# DIAGONAL_POLYPHONIC_SEQUENCER_SIMPLER_VE.net
KiCad netlist of a schematic drawn in EAGLE
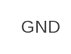
[diagram p0: schematic, sheet 1, part 1 of 2]
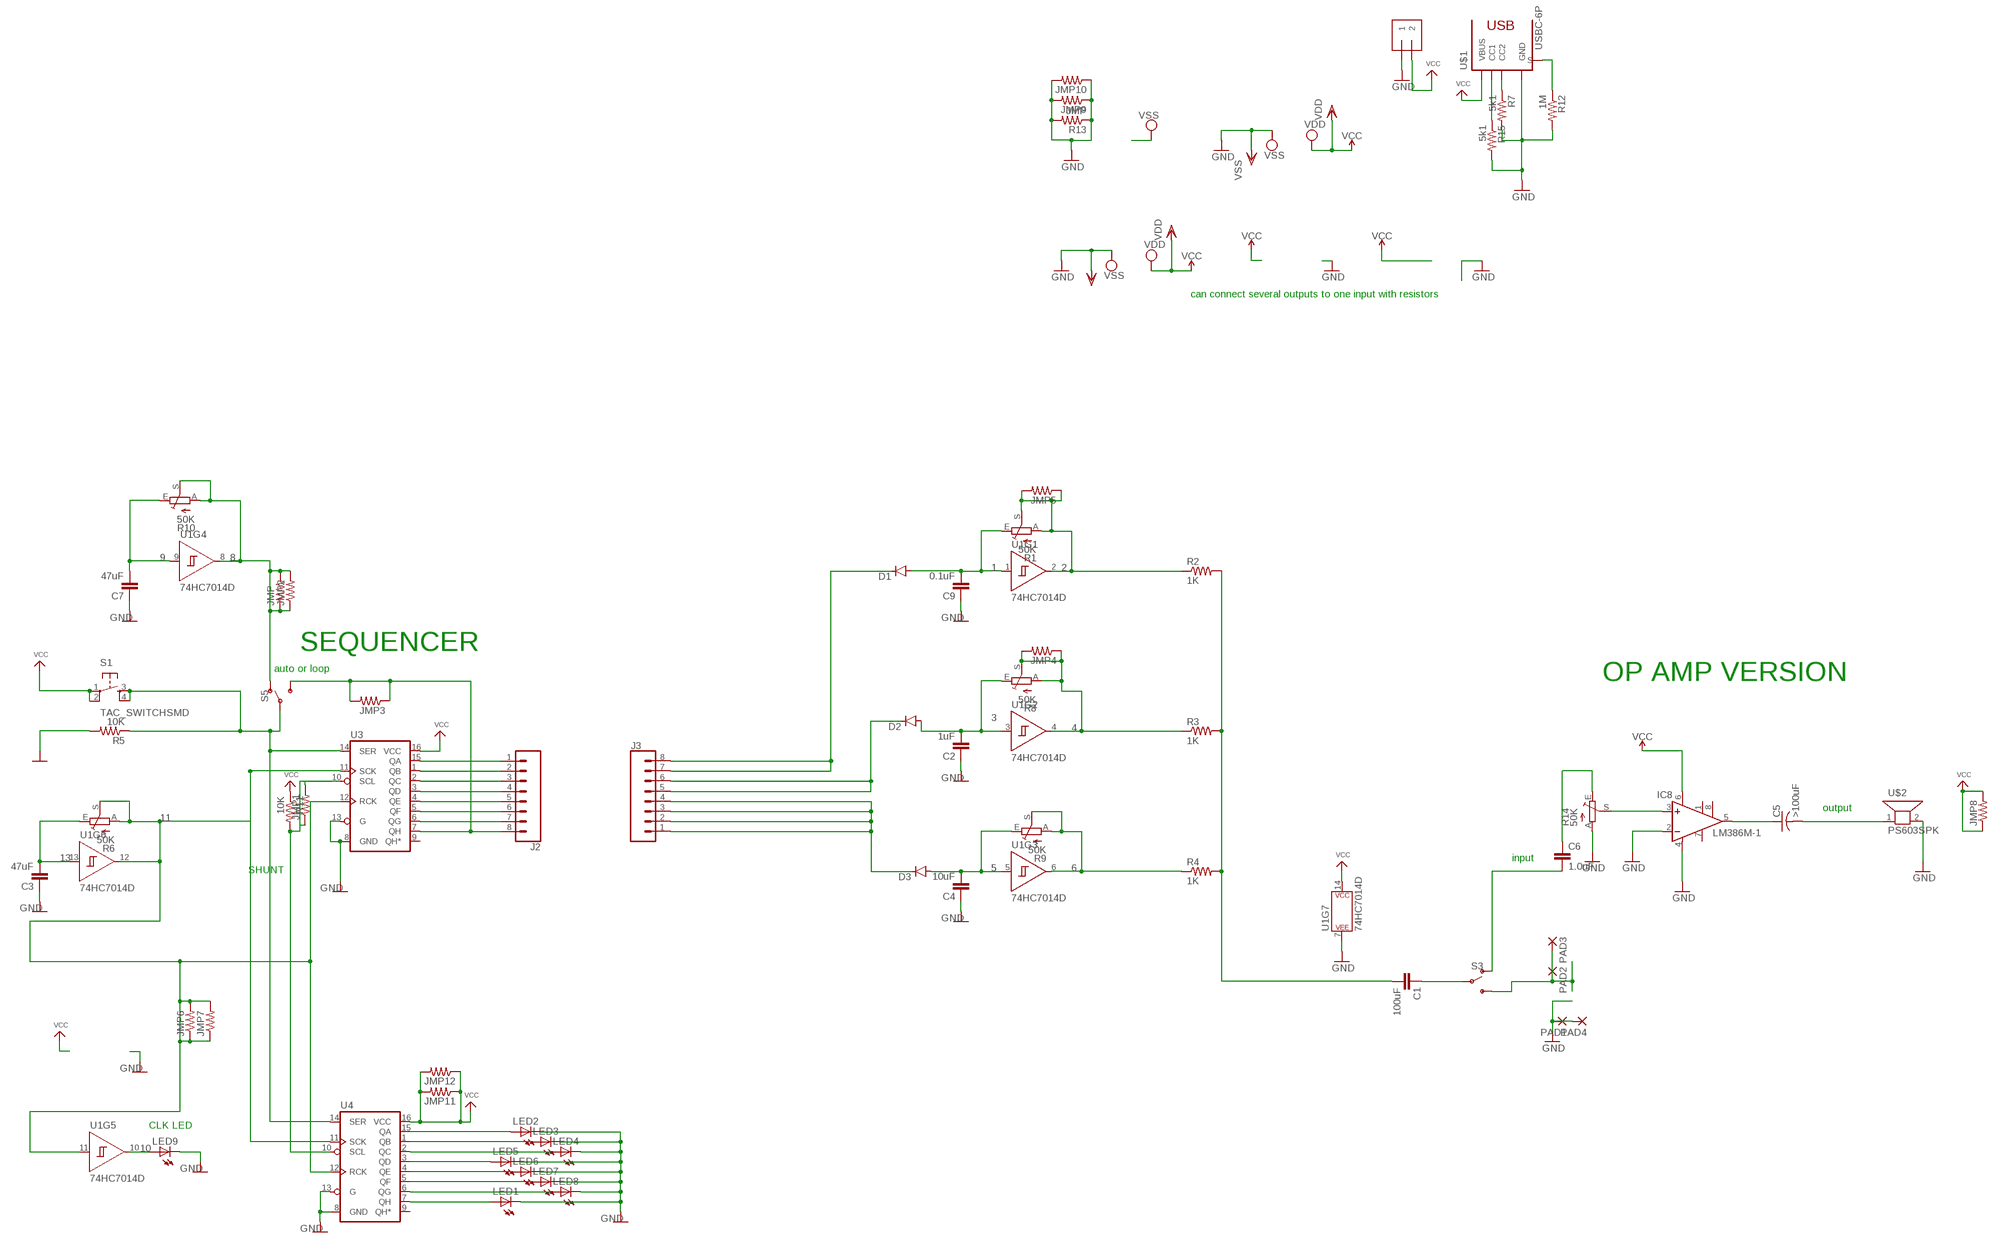
[diagram p1: schematic, sheet 1, part 2 of 2]

(export (version "E")
  (design (tool "Eeschema 10.0.6"))
  (components
    (comp (ref "C1")
      (value "100uF")
      (footprint "eagle-import:1206")
      (libsource (lib "eagle-import") (part "1.0UF-1206-50V-10%"))
    )
    (comp (ref "C2")
      (value "1uF")
      (footprint "eagle-import:1206")
      (libsource (lib "eagle-import") (part "1.0UF-1206-50V-10%"))
    )
    (comp (ref "C3")
      (value "47uF")
      (footprint "eagle-import:1206")
      (libsource (lib "eagle-import") (part "1.0UF-1206-50V-10%"))
    )
    (comp (ref "C4")
      (value "10uF")
      (footprint "eagle-import:1206")
      (libsource (lib "eagle-import") (part "1.0UF-1206-50V-10%"))
    )
    (comp (ref "C5")
      (value ">100uF")
      (footprint "eagle-import:C1206")
      (libsource (lib "eagle-import") (part "C-USC1206"))
    )
    (comp (ref "C6")
      (value "1.0uF")
      (footprint "eagle-import:1206")
      (libsource (lib "eagle-import") (part "1.0UF-1206-50V-10%"))
    )
    (comp (ref "C7")
      (value "47uF")
      (footprint "eagle-import:1206")
      (libsource (lib "eagle-import") (part "1.0UF-1206-50V-10%"))
    )
    (comp (ref "C9")
      (value "0.1uF")
      (footprint "eagle-import:1206")
      (libsource (lib "eagle-import") (part "1.0UF-1206-50V-10%"))
    )
    (comp (ref "D1")
      (value "DIODEDO214AA")
      (footprint "eagle-import:DO-214AA")
      (libsource (lib "eagle-import") (part "DIODEDO214AA"))
    )
    (comp (ref "D2")
      (value "DIODEDO214AA")
      (footprint "eagle-import:DO-214AA")
      (libsource (lib "eagle-import") (part "DIODEDO214AA"))
    )
    (comp (ref "D3")
      (value "DIODEDO214AA")
      (footprint "eagle-import:DO-214AA")
      (libsource (lib "eagle-import") (part "DIODEDO214AA"))
    )
    (comp (ref "IC8")
      (value "LM386M-1")
      (footprint "eagle-import:SO08")
      (libsource (lib "eagle-import") (part "LM386?-M1"))
    )
    (comp (ref "J1")
      (value "1X2-3.5MM")
      (footprint "eagle-import:1X2-3.5MM")
      (libsource (lib "eagle-import") (part "1X2-3.5MM"))
    )
    (comp (ref "J2")
      (value "CONN_08SMD-STRAIGHT-ALT-FEMALE")
      (footprint "eagle-import:1X08_SMD_ALT")
      (libsource (lib "eagle-import") (part "CONN_08SMD-STRAIGHT-ALT-FEMALE"))
    )
    (comp (ref "J3")
      (value "CONN_08SMD-STRAIGHT-ALT-FEMALE")
      (footprint "eagle-import:1X08_SMD_ALT")
      (libsource (lib "eagle-import") (part "CONN_08SMD-STRAIGHT-ALT-FEMALE"))
    )
    (comp (ref "JMP")
      (value "R-US_R1206")
      (footprint "eagle-import:R1206")
      (libsource (lib "eagle-import") (part "R-US_R1206"))
    )
    (comp (ref "JMP1")
      (value "R-US_R1206")
      (footprint "eagle-import:R1206")
      (libsource (lib "eagle-import") (part "R-US_R1206"))
    )
    (comp (ref "JMP2")
      (value "R-US_R1206")
      (footprint "eagle-import:R1206")
      (libsource (lib "eagle-import") (part "R-US_R1206"))
    )
    (comp (ref "JMP3")
      (value "R-US_R1206")
      (footprint "eagle-import:R1206")
      (libsource (lib "eagle-import") (part "R-US_R1206"))
    )
    (comp (ref "JMP4")
      (value "R-US_R1206")
      (footprint "eagle-import:R1206")
      (libsource (lib "eagle-import") (part "R-US_R1206"))
    )
    (comp (ref "JMP5")
      (value "R-US_R1206")
      (footprint "eagle-import:R1206")
      (libsource (lib "eagle-import") (part "R-US_R1206"))
    )
    (comp (ref "JMP6")
      (value "R-US_R1206")
      (footprint "eagle-import:R1206")
      (libsource (lib "eagle-import") (part "R-US_R1206"))
    )
    (comp (ref "JMP7")
      (value "R-US_R1206")
      (footprint "eagle-import:R1206")
      (libsource (lib "eagle-import") (part "R-US_R1206"))
    )
    (comp (ref "JMP8")
      (value "R-US_R1206")
      (footprint "eagle-import:R1206")
      (libsource (lib "eagle-import") (part "R-US_R1206"))
    )
    (comp (ref "JMP9")
      (value "R-US_R1206")
      (footprint "eagle-import:R1206")
      (libsource (lib "eagle-import") (part "R-US_R1206"))
    )
    (comp (ref "JMP10")
      (value "R-US_R1206")
      (footprint "eagle-import:R1206")
      (libsource (lib "eagle-import") (part "R-US_R1206"))
    )
    (comp (ref "JMP11")
      (value "R-US_R1206")
      (footprint "eagle-import:R1206")
      (libsource (lib "eagle-import") (part "R-US_R1206"))
    )
    (comp (ref "JMP12")
      (value "R-US_R1206")
      (footprint "eagle-import:R1206")
      (libsource (lib "eagle-import") (part "R-US_R1206"))
    )
    (comp (ref "LED1")
      (value "LEDCHIPLED_1206")
      (footprint "eagle-import:CHIPLED_1206")
      (libsource (lib "eagle-import") (part "LEDCHIPLED_1206"))
    )
    (comp (ref "LED2")
      (value "LEDCHIPLED_1206")
      (footprint "eagle-import:CHIPLED_1206")
      (libsource (lib "eagle-import") (part "LEDCHIPLED_1206"))
    )
    (comp (ref "LED3")
      (value "LEDCHIPLED_1206")
      (footprint "eagle-import:CHIPLED_1206")
      (libsource (lib "eagle-import") (part "LEDCHIPLED_1206"))
    )
    (comp (ref "LED4")
      (value "LEDCHIPLED_1206")
      (footprint "eagle-import:CHIPLED_1206")
      (libsource (lib "eagle-import") (part "LEDCHIPLED_1206"))
    )
    (comp (ref "LED5")
      (value "LEDCHIPLED_1206")
      (footprint "eagle-import:CHIPLED_1206")
      (libsource (lib "eagle-import") (part "LEDCHIPLED_1206"))
    )
    (comp (ref "LED6")
      (value "LEDCHIPLED_1206")
      (footprint "eagle-import:CHIPLED_1206")
      (libsource (lib "eagle-import") (part "LEDCHIPLED_1206"))
    )
    (comp (ref "LED7")
      (value "LEDCHIPLED_1206")
      (footprint "eagle-import:CHIPLED_1206")
      (libsource (lib "eagle-import") (part "LEDCHIPLED_1206"))
    )
    (comp (ref "LED8")
      (value "LEDCHIPLED_1206")
      (footprint "eagle-import:CHIPLED_1206")
      (libsource (lib "eagle-import") (part "LEDCHIPLED_1206"))
    )
    (comp (ref "LED9")
      (value "LEDCHIPLED_1206")
      (footprint "eagle-import:CHIPLED_1206")
      (libsource (lib "eagle-import") (part "LEDCHIPLED_1206"))
    )
    (comp (ref "PAD1")
      (value "SMD5")
      (footprint "eagle-import:SMD2,54-5,08")
      (libsource (lib "eagle-import") (part "SMD5"))
    )
    (comp (ref "PAD2")
      (value "SMD5")
      (footprint "eagle-import:SMD2,54-5,08")
      (libsource (lib "eagle-import") (part "SMD5"))
    )
    (comp (ref "PAD3")
      (value "SMD5")
      (footprint "eagle-import:SMD2,54-5,08")
      (libsource (lib "eagle-import") (part "SMD5"))
    )
    (comp (ref "PAD4")
      (value "SMD5")
      (footprint "eagle-import:SMD2,54-5,08")
      (libsource (lib "eagle-import") (part "SMD5"))
    )
    (comp (ref "R1")
      (value "50K")
      (footprint "eagle-import:CA9V")
      (libsource (lib "eagle-import") (part "TRIM_EU-CA9V"))
    )
    (comp (ref "R2")
      (value "1K")
      (footprint "eagle-import:R1206")
      (libsource (lib "eagle-import") (part "R-US_R1206"))
    )
    (comp (ref "R3")
      (value "1K")
      (footprint "eagle-import:R1206")
      (libsource (lib "eagle-import") (part "R-US_R1206"))
    )
    (comp (ref "R4")
      (value "1K")
      (footprint "eagle-import:R1206")
      (libsource (lib "eagle-import") (part "R-US_R1206"))
    )
    (comp (ref "R5")
      (value "10K")
      (footprint "eagle-import:R1206")
      (libsource (lib "eagle-import") (part "R-US_R1206"))
    )
    (comp (ref "R6")
      (value "50K")
      (footprint "eagle-import:CA9V")
      (libsource (lib "eagle-import") (part "TRIM_EU-CA9V"))
    )
    (comp (ref "R7")
      (value "5k1")
      (footprint "eagle-import:R1206")
      (libsource (lib "eagle-import") (part "R-US_R1206"))
    )
    (comp (ref "R8")
      (value "50K")
      (footprint "eagle-import:CA9V")
      (libsource (lib "eagle-import") (part "TRIM_EU-CA9V"))
    )
    (comp (ref "R9")
      (value "50K")
      (footprint "eagle-import:CA9V")
      (libsource (lib "eagle-import") (part "TRIM_EU-CA9V"))
    )
    (comp (ref "R10")
      (value "50K")
      (footprint "eagle-import:CA9V")
      (libsource (lib "eagle-import") (part "TRIM_EU-CA9V"))
    )
    (comp (ref "R11")
      (value "10K")
      (footprint "eagle-import:R1206")
      (libsource (lib "eagle-import") (part "R-US_R1206"))
    )
    (comp (ref "R12")
      (value "1M")
      (footprint "eagle-import:R1206")
      (libsource (lib "eagle-import") (part "R-US_R1206"))
    )
    (comp (ref "R13")
      (value "JMP")
      (footprint "eagle-import:R1206")
      (libsource (lib "eagle-import") (part "R-US_R1206"))
    )
    (comp (ref "R14")
      (value "50K")
      (footprint "eagle-import:CA9V")
      (libsource (lib "eagle-import") (part "TRIM_EU-CA9V"))
    )
    (comp (ref "R15")
      (value "5k1")
      (footprint "eagle-import:R1206")
      (libsource (lib "eagle-import") (part "R-US_R1206"))
    )
    (comp (ref "S1")
      (value "TAC_SWITCHSMD")
      (footprint "eagle-import:TACTILE-SWITCH-SMD")
      (libsource (lib "eagle-import") (part "TAC_SWITCHSMD"))
    )
    (comp (ref "S3")
      (value "SWITCH-SPDT-SMD-AYZ0202")
      (footprint "eagle-import:SWITCH_DPDT_SMD_AYZ0202")
      (libsource (lib "eagle-import") (part "SWITCH-SPDT-SMD-AYZ0202"))
    )
    (comp (ref "S5")
      (value "SWITCH-SPDT-SMD-AYZ0202")
      (footprint "eagle-import:SWITCH_DPDT_SMD_AYZ0202")
      (libsource (lib "eagle-import") (part "SWITCH-SPDT-SMD-AYZ0202"))
    )
    (comp (ref "U$1")
      (value "USBC-6P")
      (footprint "eagle-import:USCX-06FX-XXMX-01")
      (libsource (lib "eagle-import") (part "USBC-6P"))
    )
    (comp (ref "U$2")
      (value "PS603SPK")
      (footprint "eagle-import:PS603")
      (libsource (lib "eagle-import") (part "PS603SPK"))
    )
    (comp (ref "U1")
      (value "74HC7014D")
      (footprint "eagle-import:SO14")
      (libsource (lib "eagle-import") (part "747014DHC"))
    )
    (comp (ref "U3")
      (value "74595")
      (footprint "eagle-import:TSSOP16")
      (libsource (lib "eagle-import") (part "74595"))
    )
    (comp (ref "U4")
      (value "74595")
      (footprint "eagle-import:TSSOP16")
      (libsource (lib "eagle-import") (part "74595"))
    )
  )
  (nets
    (net (code "1") (name "/1") (class "Default")
      (node (ref "C9") (pin "2") (pinfunction "2_2") (pintype "passive"))
      (node (ref "D1") (pin "A") (pinfunction "A_A") (pintype "passive"))
      (node (ref "R1") (pin "E") (pinfunction "E_E") (pintype "passive"))
      (node (ref "U1") (pin "1") (pinfunction "A_1") (pintype "bidirectional"))
    )
    (net (code "2") (name "/2") (class "Default")
      (node (ref "JMP5") (pin "1") (pinfunction "1_1") (pintype "passive"))
      (node (ref "JMP5") (pin "2") (pinfunction "2_2") (pintype "passive"))
      (node (ref "R1") (pin "A") (pinfunction "A_A") (pintype "passive"))
      (node (ref "R1") (pin "S") (pinfunction "S_S") (pintype "passive"))
      (node (ref "R2") (pin "1") (pinfunction "1_1") (pintype "passive"))
      (node (ref "U1") (pin "2") (pinfunction "Y_2") (pintype "bidirectional"))
    )
    (net (code "3") (name "/3") (class "Default")
      (node (ref "C2") (pin "2") (pinfunction "2_2") (pintype "passive"))
      (node (ref "D2") (pin "A") (pinfunction "A_A") (pintype "passive"))
      (node (ref "R8") (pin "E") (pinfunction "E_E") (pintype "passive"))
      (node (ref "U1") (pin "3") (pinfunction "A_3") (pintype "bidirectional"))
    )
    (net (code "4") (name "/4") (class "Default")
      (node (ref "JMP4") (pin "1") (pinfunction "1_1") (pintype "passive"))
      (node (ref "JMP4") (pin "2") (pinfunction "2_2") (pintype "passive"))
      (node (ref "R3") (pin "1") (pinfunction "1_1") (pintype "passive"))
      (node (ref "R8") (pin "A") (pinfunction "A_A") (pintype "passive"))
      (node (ref "R8") (pin "S") (pinfunction "S_S") (pintype "passive"))
      (node (ref "U1") (pin "4") (pinfunction "Y_4") (pintype "bidirectional"))
    )
    (net (code "5") (name "/5") (class "Default")
      (node (ref "C4") (pin "2") (pinfunction "2_2") (pintype "passive"))
      (node (ref "D3") (pin "A") (pinfunction "A_A") (pintype "passive"))
      (node (ref "R9") (pin "E") (pinfunction "E_E") (pintype "passive"))
      (node (ref "U1") (pin "5") (pinfunction "A_5") (pintype "bidirectional"))
    )
    (net (code "6") (name "/6") (class "Default")
      (node (ref "R4") (pin "1") (pinfunction "1_1") (pintype "passive"))
      (node (ref "R9") (pin "A") (pinfunction "A_A") (pintype "passive"))
      (node (ref "R9") (pin "S") (pinfunction "S_S") (pintype "passive"))
      (node (ref "U1") (pin "6") (pinfunction "Y_6") (pintype "bidirectional"))
    )
    (net (code "7") (name "/8") (class "Default")
      (node (ref "JMP") (pin "1") (pinfunction "1_1") (pintype "passive"))
      (node (ref "JMP") (pin "2") (pinfunction "2_2") (pintype "passive"))
      (node (ref "JMP2") (pin "1") (pinfunction "1_1") (pintype "passive"))
      (node (ref "JMP2") (pin "2") (pinfunction "2_2") (pintype "passive"))
      (node (ref "R10") (pin "A") (pinfunction "A_A") (pintype "passive"))
      (node (ref "R10") (pin "S") (pinfunction "S_S") (pintype "passive"))
      (node (ref "S5") (pin "1") (pinfunction "O_1") (pintype "passive"))
      (node (ref "U1") (pin "8") (pinfunction "Y_8") (pintype "bidirectional"))
    )
    (net (code "8") (name "/9") (class "Default")
      (node (ref "C7") (pin "2") (pinfunction "2_2") (pintype "passive"))
      (node (ref "R10") (pin "E") (pinfunction "E_E") (pintype "passive"))
      (node (ref "U1") (pin "9") (pinfunction "A_9") (pintype "bidirectional"))
    )
    (net (code "9") (name "/10") (class "Default")
      (node (ref "LED9") (pin "A") (pinfunction "A_A") (pintype "passive"))
      (node (ref "U1") (pin "10") (pinfunction "Y_10") (pintype "bidirectional"))
    )
    (net (code "10") (name "/11") (class "Default")
      (node (ref "JMP6") (pin "1") (pinfunction "1_1") (pintype "passive"))
      (node (ref "JMP6") (pin "2") (pinfunction "2_2") (pintype "passive"))
      (node (ref "JMP7") (pin "1") (pinfunction "1_1") (pintype "passive"))
      (node (ref "JMP7") (pin "2") (pinfunction "2_2") (pintype "passive"))
      (node (ref "R6") (pin "A") (pinfunction "A_A") (pintype "passive"))
      (node (ref "R6") (pin "S") (pinfunction "S_S") (pintype "passive"))
      (node (ref "U1") (pin "11") (pinfunction "A_11") (pintype "bidirectional"))
      (node (ref "U1") (pin "12") (pinfunction "Y_12") (pintype "bidirectional"))
      (node (ref "U3") (pin "11") (pinfunction "SCK_11") (pintype "input"))
      (node (ref "U3") (pin "12") (pinfunction "RCK_12") (pintype "input"))
      (node (ref "U4") (pin "11") (pinfunction "SCK_11") (pintype "input"))
      (node (ref "U4") (pin "12") (pinfunction "RCK_12") (pintype "input"))
    )
    (net (code "11") (name "/13") (class "Default")
      (node (ref "C3") (pin "2") (pinfunction "2_2") (pintype "passive"))
      (node (ref "R6") (pin "E") (pinfunction "E_E") (pintype "passive"))
      (node (ref "U1") (pin "13") (pinfunction "A_13") (pintype "bidirectional"))
    )
    (net (code "12") (name "GND") (class "Default")
      (node (ref "C2") (pin "1") (pinfunction "1_1") (pintype "passive"))
      (node (ref "C3") (pin "1") (pinfunction "1_1") (pintype "passive"))
      (node (ref "C4") (pin "1") (pinfunction "1_1") (pintype "passive"))
      (node (ref "C7") (pin "1") (pinfunction "1_1") (pintype "passive"))
      (node (ref "C9") (pin "1") (pinfunction "1_1") (pintype "passive"))
      (node (ref "IC8") (pin "2") (pinfunction "-IN_2") (pintype "input"))
      (node (ref "IC8") (pin "4") (pinfunction "GND_4") (pintype "power_in"))
      (node (ref "J1") (pin "1") (pinfunction "1_1") (pintype "passive"))
      (node (ref "JMP10") (pin "1") (pinfunction "1_1") (pintype "passive"))
      (node (ref "JMP10") (pin "2") (pinfunction "2_2") (pintype "passive"))
      (node (ref "JMP9") (pin "1") (pinfunction "1_1") (pintype "passive"))
      (node (ref "JMP9") (pin "2") (pinfunction "2_2") (pintype "passive"))
      (node (ref "LED1") (pin "C") (pinfunction "C_C") (pintype "passive"))
      (node (ref "LED2") (pin "C") (pinfunction "C_C") (pintype "passive"))
      (node (ref "LED3") (pin "C") (pinfunction "C_C") (pintype "passive"))
      (node (ref "LED4") (pin "C") (pinfunction "C_C") (pintype "passive"))
      (node (ref "LED5") (pin "C") (pinfunction "C_C") (pintype "passive"))
      (node (ref "LED6") (pin "C") (pinfunction "C_C") (pintype "passive"))
      (node (ref "LED7") (pin "C") (pinfunction "C_C") (pintype "passive"))
      (node (ref "LED8") (pin "C") (pinfunction "C_C") (pintype "passive"))
      (node (ref "LED9") (pin "C") (pinfunction "C_C") (pintype "passive"))
      (node (ref "PAD1") (pin "1") (pinfunction "P_1") (pintype "passive"))
      (node (ref "PAD4") (pin "1") (pinfunction "P_1") (pintype "passive"))
      (node (ref "R12") (pin "2") (pinfunction "2_2") (pintype "passive"))
      (node (ref "R13") (pin "1") (pinfunction "1_1") (pintype "passive"))
      (node (ref "R13") (pin "2") (pinfunction "2_2") (pintype "passive"))
      (node (ref "R14") (pin "A") (pinfunction "A_A") (pintype "passive"))
      (node (ref "R15") (pin "2") (pinfunction "2_2") (pintype "passive"))
      (node (ref "R5") (pin "2") (pinfunction "2_2") (pintype "passive"))
      (node (ref "R7") (pin "2") (pinfunction "2_2") (pintype "passive"))
      (node (ref "U$1") (pin "GND1") (pinfunction "GND_GND1") (pintype "power_in"))
      (node (ref "U$1") (pin "GND2") (pinfunction "GND_GND2") (pintype "power_in"))
      (node (ref "U$2") (pin "2") (pinfunction "2_2") (pintype "passive"))
      (node (ref "U1") (pin "7") (pinfunction "P$V-_7") (pintype "bidirectional"))
      (node (ref "U3") (pin "13") (pinfunction "G_13") (pintype "input"))
      (node (ref "U3") (pin "8") (pinfunction "GND_8") (pintype "power_in"))
      (node (ref "U4") (pin "13") (pinfunction "G_13") (pintype "input"))
      (node (ref "U4") (pin "8") (pinfunction "GND_8") (pintype "power_in"))
    )
    (net (code "13") (name "Net-(C1-Pad2)") (class "Default")
      (node (ref "C1") (pin "2") (pinfunction "2_2") (pintype "passive"))
      (node (ref "R2") (pin "2") (pinfunction "2_2") (pintype "passive"))
      (node (ref "R3") (pin "2") (pinfunction "2_2") (pintype "passive"))
      (node (ref "R4") (pin "2") (pinfunction "2_2") (pintype "passive"))
    )
    (net (code "14") (name "Net-(C5-Pad2)") (class "Default")
      (node (ref "C5") (pin "2") (pinfunction "2_2") (pintype "passive"))
      (node (ref "U$2") (pin "1") (pinfunction "1_1") (pintype "passive"))
    )
    (net (code "15") (name "Net-(C6-Pad1)") (class "Default")
      (node (ref "C6") (pin "1") (pinfunction "1_1") (pintype "passive"))
      (node (ref "R14") (pin "E") (pinfunction "E_E") (pintype "passive"))
    )
    (net (code "16") (name "Net-(D1-PadC)") (class "Default")
      (node (ref "D1") (pin "C") (pinfunction "C_C") (pintype "passive"))
      (node (ref "J3") (pin "7") (pinfunction "7_7") (pintype "passive"))
      (node (ref "J3") (pin "8") (pinfunction "8_8") (pintype "passive"))
    )
    (net (code "17") (name "Net-(D2-PadC)") (class "Default")
      (node (ref "D2") (pin "C") (pinfunction "C_C") (pintype "passive"))
      (node (ref "J3") (pin "5") (pinfunction "5_5") (pintype "passive"))
      (node (ref "J3") (pin "6") (pinfunction "6_6") (pintype "passive"))
    )
    (net (code "18") (name "Net-(D3-PadC)") (class "Default")
      (node (ref "D3") (pin "C") (pinfunction "C_C") (pintype "passive"))
      (node (ref "J3") (pin "1") (pinfunction "1_1") (pintype "passive"))
      (node (ref "J3") (pin "2") (pinfunction "2_2") (pintype "passive"))
      (node (ref "J3") (pin "3") (pinfunction "3_3") (pintype "passive"))
      (node (ref "J3") (pin "4") (pinfunction "4_4") (pintype "passive"))
    )
    (net (code "19") (name "Net-(IC8-+IN)") (class "Default")
      (node (ref "IC8") (pin "3") (pinfunction "+IN_3") (pintype "input"))
      (node (ref "R14") (pin "S") (pinfunction "S_S") (pintype "passive"))
    )
    (net (code "20") (name "Net-(IC8-OUT)") (class "Default")
      (node (ref "C5") (pin "1") (pinfunction "1_1") (pintype "passive"))
      (node (ref "IC8") (pin "5") (pinfunction "OUT_5") (pintype "output"))
    )
    (net (code "21") (name "Net-(PAD2-P)") (class "Default")
      (node (ref "PAD2") (pin "1") (pinfunction "P_1") (pintype "passive"))
      (node (ref "PAD3") (pin "1") (pinfunction "P_1") (pintype "passive"))
      (node (ref "S3") (pin "3") (pinfunction "S_3") (pintype "passive"))
    )
    (net (code "22") (name "Net-(R7-Pad1)") (class "Default")
      (node (ref "R7") (pin "1") (pinfunction "1_1") (pintype "passive"))
      (node (ref "U$1") (pin "CC2") (pinfunction "CC2_CC2") (pintype "bidirectional"))
    )
    (net (code "23") (name "Net-(R12-Pad1)") (class "Default")
      (node (ref "R12") (pin "1") (pinfunction "1_1") (pintype "passive"))
      (node (ref "U$1") (pin "SHIELD1") (pinfunction "S_SHIELD1") (pintype "passive"))
      (node (ref "U$1") (pin "SHIELD2") (pinfunction "S_SHIELD2") (pintype "passive"))
      (node (ref "U$1") (pin "SHIELD3") (pinfunction "S_SHIELD3") (pintype "passive"))
      (node (ref "U$1") (pin "SHIELD4") (pinfunction "S_SHIELD4") (pintype "passive"))
    )
    (net (code "24") (name "Net-(R15-Pad1)") (class "Default")
      (node (ref "R15") (pin "1") (pinfunction "1_1") (pintype "passive"))
      (node (ref "U$1") (pin "CC1") (pinfunction "CC1_CC1") (pintype "bidirectional"))
    )
    (net (code "25") (name "Net-(S3-O)") (class "Default")
      (node (ref "C6") (pin "2") (pinfunction "2_2") (pintype "passive"))
      (node (ref "S3") (pin "1") (pinfunction "O_1") (pintype "passive"))
    )
    (net (code "26") (name "Net-(S3-P)") (class "Default")
      (node (ref "C1") (pin "1") (pinfunction "1_1") (pintype "passive"))
      (node (ref "S3") (pin "2") (pinfunction "P_2") (pintype "passive"))
    )
    (net (code "27") (name "Net-(S5-P)") (class "Default")
      (node (ref "R5") (pin "1") (pinfunction "1_1") (pintype "passive"))
      (node (ref "S1") (pin "3") (pinfunction "3_3") (pintype "passive"))
      (node (ref "S1") (pin "4") (pinfunction "4_4") (pintype "passive"))
      (node (ref "S5") (pin "2") (pinfunction "P_2") (pintype "passive"))
      (node (ref "U3") (pin "14") (pinfunction "SER_14") (pintype "input"))
      (node (ref "U4") (pin "14") (pinfunction "SER_14") (pintype "input"))
    )
    (net (code "28") (name "Net-(S5-S)") (class "Default")
      (node (ref "J2") (pin "8") (pinfunction "8_8") (pintype "passive"))
      (node (ref "JMP3") (pin "1") (pinfunction "1_1") (pintype "passive"))
      (node (ref "JMP3") (pin "2") (pinfunction "2_2") (pintype "passive"))
      (node (ref "S5") (pin "3") (pinfunction "S_3") (pintype "passive"))
      (node (ref "U3") (pin "7") (pinfunction "QH_7") (pintype "tri_state"))
    )
    (net (code "29") (name "Net-(U3-QA)") (class "Default")
      (node (ref "J2") (pin "1") (pinfunction "1_1") (pintype "passive"))
      (node (ref "U3") (pin "15") (pinfunction "QA_15") (pintype "tri_state"))
    )
    (net (code "30") (name "Net-(U3-QB)") (class "Default")
      (node (ref "J2") (pin "2") (pinfunction "2_2") (pintype "passive"))
      (node (ref "U3") (pin "1") (pinfunction "QB_1") (pintype "tri_state"))
    )
    (net (code "31") (name "Net-(U3-QC)") (class "Default")
      (node (ref "J2") (pin "3") (pinfunction "3_3") (pintype "passive"))
      (node (ref "U3") (pin "2") (pinfunction "QC_2") (pintype "tri_state"))
    )
    (net (code "32") (name "Net-(U3-QD)") (class "Default")
      (node (ref "J2") (pin "4") (pinfunction "4_4") (pintype "passive"))
      (node (ref "U3") (pin "3") (pinfunction "QD_3") (pintype "tri_state"))
    )
    (net (code "33") (name "Net-(U3-QE)") (class "Default")
      (node (ref "J2") (pin "5") (pinfunction "5_5") (pintype "passive"))
      (node (ref "U3") (pin "4") (pinfunction "QE_4") (pintype "tri_state"))
    )
    (net (code "34") (name "Net-(U3-QF)") (class "Default")
      (node (ref "J2") (pin "6") (pinfunction "6_6") (pintype "passive"))
      (node (ref "U3") (pin "5") (pinfunction "QF_5") (pintype "tri_state"))
    )
    (net (code "35") (name "Net-(U3-QG)") (class "Default")
      (node (ref "J2") (pin "7") (pinfunction "7_7") (pintype "passive"))
      (node (ref "U3") (pin "6") (pinfunction "QG_6") (pintype "tri_state"))
    )
    (net (code "36") (name "Net-(U3-SCL)") (class "Default")
      (node (ref "JMP1") (pin "1") (pinfunction "1_1") (pintype "passive"))
      (node (ref "JMP1") (pin "2") (pinfunction "2_2") (pintype "passive"))
      (node (ref "R11") (pin "2") (pinfunction "2_2") (pintype "passive"))
      (node (ref "U3") (pin "10") (pinfunction "SCL_10") (pintype "input"))
      (node (ref "U4") (pin "10") (pinfunction "SCL_10") (pintype "input"))
    )
    (net (code "37") (name "Net-(U4-QA)") (class "Default")
      (node (ref "LED2") (pin "A") (pinfunction "A_A") (pintype "passive"))
      (node (ref "U4") (pin "15") (pinfunction "QA_15") (pintype "tri_state"))
    )
    (net (code "38") (name "Net-(U4-QB)") (class "Default")
      (node (ref "LED3") (pin "A") (pinfunction "A_A") (pintype "passive"))
      (node (ref "U4") (pin "1") (pinfunction "QB_1") (pintype "tri_state"))
    )
    (net (code "39") (name "Net-(U4-QC)") (class "Default")
      (node (ref "LED4") (pin "A") (pinfunction "A_A") (pintype "passive"))
      (node (ref "U4") (pin "2") (pinfunction "QC_2") (pintype "tri_state"))
    )
    (net (code "40") (name "Net-(U4-QD)") (class "Default")
      (node (ref "LED5") (pin "A") (pinfunction "A_A") (pintype "passive"))
      (node (ref "U4") (pin "3") (pinfunction "QD_3") (pintype "tri_state"))
    )
    (net (code "41") (name "Net-(U4-QE)") (class "Default")
      (node (ref "LED6") (pin "A") (pinfunction "A_A") (pintype "passive"))
      (node (ref "U4") (pin "4") (pinfunction "QE_4") (pintype "tri_state"))
    )
    (net (code "42") (name "Net-(U4-QF)") (class "Default")
      (node (ref "LED7") (pin "A") (pinfunction "A_A") (pintype "passive"))
      (node (ref "U4") (pin "5") (pinfunction "QF_5") (pintype "tri_state"))
    )
    (net (code "43") (name "Net-(U4-QG)") (class "Default")
      (node (ref "LED8") (pin "A") (pinfunction "A_A") (pintype "passive"))
      (node (ref "U4") (pin "6") (pinfunction "QG_6") (pintype "tri_state"))
    )
    (net (code "44") (name "Net-(U4-QH)") (class "Default")
      (node (ref "LED1") (pin "A") (pinfunction "A_A") (pintype "passive"))
      (node (ref "U4") (pin "7") (pinfunction "QH_7") (pintype "tri_state"))
    )
    (net (code "45") (name "VCC") (class "Default")
      (node (ref "IC8") (pin "6") (pinfunction "VS_6") (pintype "power_in"))
      (node (ref "J1") (pin "2") (pinfunction "2_2") (pintype "passive"))
      (node (ref "JMP11") (pin "1") (pinfunction "1_1") (pintype "passive"))
      (node (ref "JMP11") (pin "2") (pinfunction "2_2") (pintype "passive"))
      (node (ref "JMP12") (pin "1") (pinfunction "1_1") (pintype "passive"))
      (node (ref "JMP12") (pin "2") (pinfunction "2_2") (pintype "passive"))
      (node (ref "JMP8") (pin "1") (pinfunction "1_1") (pintype "passive"))
      (node (ref "JMP8") (pin "2") (pinfunction "2_2") (pintype "passive"))
      (node (ref "R11") (pin "1") (pinfunction "1_1") (pintype "passive"))
      (node (ref "S1") (pin "1") (pinfunction "1_1") (pintype "passive"))
      (node (ref "S1") (pin "2") (pinfunction "2_2") (pintype "passive"))
      (node (ref "U$1") (pin "VBUS1") (pinfunction "VBUS_VBUS1") (pintype "power_in"))
      (node (ref "U$1") (pin "VBUS2") (pinfunction "VBUS_VBUS2") (pintype "power_in"))
      (node (ref "U1") (pin "14") (pinfunction "P$V+_14") (pintype "bidirectional"))
      (node (ref "U3") (pin "16") (pinfunction "VCC_16") (pintype "power_in"))
      (node (ref "U4") (pin "16") (pinfunction "VCC_16") (pintype "power_in"))
    )
    (net (code "46") (name "unconnected-(IC8-BYPASS-Pad7)") (class "Default")
      (node (ref "IC8") (pin "7") (pinfunction "BYPASS_7") (pintype "passive"))
    )
    (net (code "47") (name "unconnected-(IC8-GAIN-Pad1)") (class "Default")
      (node (ref "IC8") (pin "1") (pinfunction "GAIN_1") (pintype "passive"))
    )
    (net (code "48") (name "unconnected-(IC8-GAIN-Pad8)") (class "Default")
      (node (ref "IC8") (pin "8") (pinfunction "GAIN_8") (pintype "passive"))
    )
    (net (code "49") (name "unconnected-(U3-QH*-Pad9)") (class "Default")
      (node (ref "U3") (pin "9") (pinfunction "QH*_9") (pintype "tri_state"))
    )
    (net (code "50") (name "unconnected-(U4-QH*-Pad9)") (class "Default")
      (node (ref "U4") (pin "9") (pinfunction "QH*_9") (pintype "tri_state"))
    )
  )
)
